# Shield.net
KiCad netlist of a schematic drawn in EAGLE
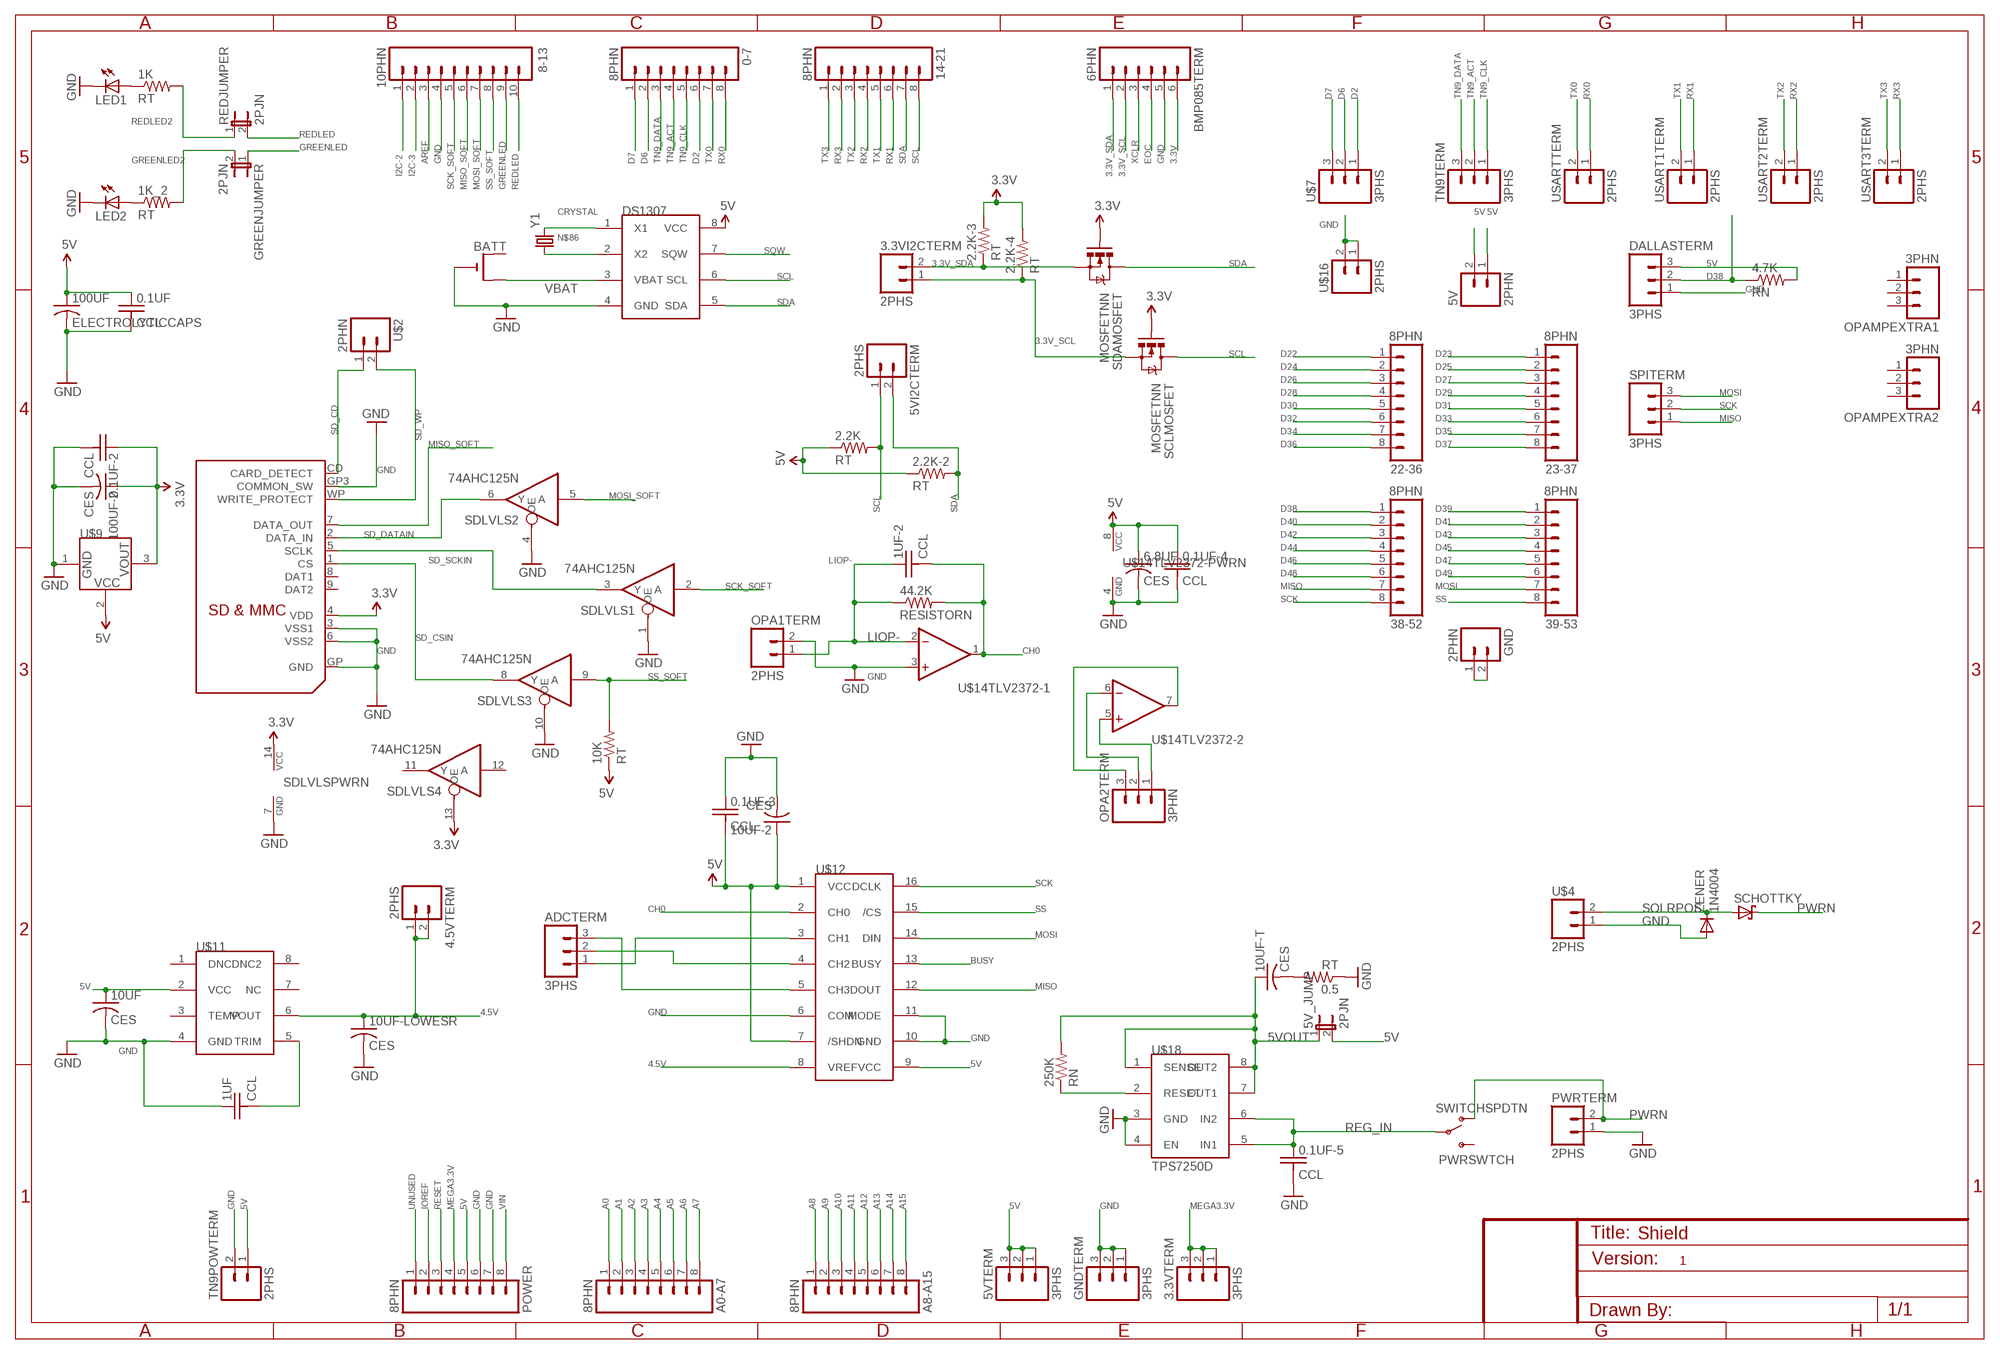
[diagram p0: schematic, sheet 1]

(export (version "E")
  (design (tool "Eeschema 10.0.6"))
  (components
    (comp (ref "0-7")
      (value "8PHN")
      (footprint "eagle-import:8PH")
      (libsource (lib "eagle-import") (part "8PHN"))
    )
    (comp (ref "0.1UF")
      (value "CCL")
      (footprint "eagle-import:C025-025X050")
      (libsource (lib "eagle-import") (part "CCL"))
    )
    (comp (ref "0.1UF-2")
      (value "CCL")
      (footprint "eagle-import:C025-025X050")
      (libsource (lib "eagle-import") (part "CCL"))
    )
    (comp (ref "0.1UF-3")
      (value "CCL")
      (footprint "eagle-import:C025-025X050")
      (libsource (lib "eagle-import") (part "CCL"))
    )
    (comp (ref "0.1UF-4")
      (value "CCL")
      (footprint "eagle-import:C025-025X050")
      (libsource (lib "eagle-import") (part "CCL"))
    )
    (comp (ref "0.1UF-5")
      (value "CCL")
      (footprint "eagle-import:C025-025X050")
      (libsource (lib "eagle-import") (part "CCL"))
    )
    (comp (ref "0.5")
      (value "RT")
      (footprint "eagle-import:0207_7")
      (libsource (lib "eagle-import") (part "RT"))
    )
    (comp (ref "1K")
      (value "RT")
      (footprint "eagle-import:0207_7")
      (libsource (lib "eagle-import") (part "RT"))
    )
    (comp (ref "1K_2")
      (value "RT")
      (footprint "eagle-import:0207_7")
      (libsource (lib "eagle-import") (part "RT"))
    )
    (comp (ref "1UF")
      (value "CCL")
      (footprint "eagle-import:C025-025X050")
      (libsource (lib "eagle-import") (part "CCL"))
    )
    (comp (ref "1UF-2")
      (value "CCL")
      (footprint "eagle-import:C025-025X050")
      (libsource (lib "eagle-import") (part "CCL"))
    )
    (comp (ref "2.2K")
      (value "RT")
      (footprint "eagle-import:0207_7")
      (libsource (lib "eagle-import") (part "RT"))
    )
    (comp (ref "2.2K-2")
      (value "RT")
      (footprint "eagle-import:0207_7")
      (libsource (lib "eagle-import") (part "RT"))
    )
    (comp (ref "2.2K-3")
      (value "RT")
      (footprint "eagle-import:0207_7")
      (libsource (lib "eagle-import") (part "RT"))
    )
    (comp (ref "2.2K-4")
      (value "RT")
      (footprint "eagle-import:0207_7")
      (libsource (lib "eagle-import") (part "RT"))
    )
    (comp (ref "3.3VI2CTERM")
      (value "2PHS")
      (footprint "eagle-import:SCREWTERMINAL-3.5MM-2_LOCK")
      (libsource (lib "eagle-import") (part "2PHS"))
    )
    (comp (ref "3.3VTERM")
      (value "3PHS")
      (footprint "eagle-import:SCREWTERMINAL-3.5MM-3_LOCK.007S")
      (libsource (lib "eagle-import") (part "3PHS"))
    )
    (comp (ref "4.5VTERM")
      (value "2PHS")
      (footprint "eagle-import:SCREWTERMINAL-3.5MM-2_LOCK")
      (libsource (lib "eagle-import") (part "2PHS"))
    )
    (comp (ref "4.7K")
      (value "RN")
      (footprint "eagle-import:0207_10")
      (libsource (lib "eagle-import") (part "RN"))
    )
    (comp (ref "5V")
      (value "2PHN")
      (footprint "eagle-import:2PH")
      (libsource (lib "eagle-import") (part "2PHN"))
    )
    (comp (ref "5VI2CTERM")
      (value "2PHS")
      (footprint "eagle-import:SCREWTERMINAL-3.5MM-2_LOCK")
      (libsource (lib "eagle-import") (part "2PHS"))
    )
    (comp (ref "5VTERM")
      (value "3PHS")
      (footprint "eagle-import:SCREWTERMINAL-3.5MM-3_LOCK.007S")
      (libsource (lib "eagle-import") (part "3PHS"))
    )
    (comp (ref "5V_JUMP")
      (value "2PJN")
      (footprint "eagle-import:2PH")
      (libsource (lib "eagle-import") (part "2PJN"))
    )
    (comp (ref "6.8UF")
      (value "CES")
      (footprint "eagle-import:E2,5-5")
      (libsource (lib "eagle-import") (part "CES"))
    )
    (comp (ref "8-13")
      (value "10PHN")
      (footprint "eagle-import:10PH")
      (libsource (lib "eagle-import") (part "10PHN"))
    )
    (comp (ref "10K")
      (value "RT")
      (footprint "eagle-import:0207_7")
      (libsource (lib "eagle-import") (part "RT"))
    )
    (comp (ref "10UF")
      (value "CES")
      (footprint "eagle-import:E2,5-5")
      (libsource (lib "eagle-import") (part "CES"))
    )
    (comp (ref "10UF-2")
      (value "CES")
      (footprint "eagle-import:E2,5-5")
      (libsource (lib "eagle-import") (part "CES"))
    )
    (comp (ref "10UF-LOWESR")
      (value "CES")
      (footprint "eagle-import:E2,5-5")
      (libsource (lib "eagle-import") (part "CES"))
    )
    (comp (ref "10UF-T")
      (value "CES")
      (footprint "eagle-import:E2,5-5")
      (libsource (lib "eagle-import") (part "CES"))
    )
    (comp (ref "14-21")
      (value "8PHN")
      (footprint "eagle-import:8PH")
      (libsource (lib "eagle-import") (part "8PHN"))
    )
    (comp (ref "22-36")
      (value "8PHN")
      (footprint "eagle-import:8PH")
      (libsource (lib "eagle-import") (part "8PHN"))
    )
    (comp (ref "23-37")
      (value "8PHN")
      (footprint "eagle-import:8PH")
      (libsource (lib "eagle-import") (part "8PHN"))
    )
    (comp (ref "38-52")
      (value "8PHN")
      (footprint "eagle-import:8PH")
      (libsource (lib "eagle-import") (part "8PHN"))
    )
    (comp (ref "39-53")
      (value "8PHN")
      (footprint "eagle-import:8PH")
      (libsource (lib "eagle-import") (part "8PHN"))
    )
    (comp (ref "44.2K")
      (value "RESISTORN")
      (footprint "eagle-import:0207_10")
      (libsource (lib "eagle-import") (part "RESISTORN"))
    )
    (comp (ref "100UF")
      (value "ELECTROLYTICCAPS")
      (footprint "eagle-import:E2,5-5")
      (libsource (lib "eagle-import") (part "ELECTROLYTICCAPS"))
    )
    (comp (ref "100UF-2")
      (value "CES")
      (footprint "eagle-import:E2,5-5")
      (libsource (lib "eagle-import") (part "CES"))
    )
    (comp (ref "250K")
      (value "RN")
      (footprint "eagle-import:0207_10")
      (libsource (lib "eagle-import") (part "RN"))
    )
    (comp (ref "A0-A7")
      (value "8PHN")
      (footprint "eagle-import:8PH")
      (libsource (lib "eagle-import") (part "8PHN"))
    )
    (comp (ref "A8-A15")
      (value "8PHN")
      (footprint "eagle-import:8PH")
      (libsource (lib "eagle-import") (part "8PHN"))
    )
    (comp (ref "ADCTERM")
      (value "3PHS")
      (footprint "eagle-import:SCREWTERMINAL-3.5MM-3_LOCK.007S")
      (libsource (lib "eagle-import") (part "3PHS"))
    )
    (comp (ref "BATT")
      (value "CR1220THM")
      (footprint "eagle-import:CR1220-THM")
      (libsource (lib "eagle-import") (part "CR1220THM"))
    )
    (comp (ref "BMP085TERM")
      (value "6PHN")
      (footprint "eagle-import:6PH")
      (libsource (lib "eagle-import") (part "6PHN"))
    )
    (comp (ref "DALLASTERM")
      (value "3PHS")
      (footprint "eagle-import:SCREWTERMINAL-3.5MM-3_LOCK.007S")
      (libsource (lib "eagle-import") (part "3PHS"))
    )
    (comp (ref "DS1307")
      (value "DS1307P")
      (footprint "eagle-import:DIL8")
      (libsource (lib "eagle-import") (part "DS1307P"))
    )
    (comp (ref "GND")
      (value "2PHN")
      (footprint "eagle-import:2PH")
      (libsource (lib "eagle-import") (part "2PHN"))
    )
    (comp (ref "GNDTERM")
      (value "3PHS")
      (footprint "eagle-import:SCREWTERMINAL-3.5MM-3_LOCK.007S")
      (libsource (lib "eagle-import") (part "3PHS"))
    )
    (comp (ref "GREENJUMPER")
      (value "2PJN")
      (footprint "eagle-import:2PH")
      (libsource (lib "eagle-import") (part "2PJN"))
    )
    (comp (ref "LED1")
      (value "LED3MM")
      (footprint "eagle-import:LED3MM")
      (libsource (lib "eagle-import") (part "LED3MM"))
    )
    (comp (ref "LED2")
      (value "LED3MM")
      (footprint "eagle-import:LED3MM")
      (libsource (lib "eagle-import") (part "LED3MM"))
    )
    (comp (ref "OPA1TERM")
      (value "2PHS")
      (footprint "eagle-import:SCREWTERMINAL-3.5MM-2_LOCK")
      (libsource (lib "eagle-import") (part "2PHS"))
    )
    (comp (ref "OPA2TERM")
      (value "3PHN")
      (footprint "eagle-import:3PH")
      (libsource (lib "eagle-import") (part "3PHN"))
    )
    (comp (ref "OPAMPEXTRA1")
      (value "3PHN")
      (footprint "eagle-import:3PH")
      (libsource (lib "eagle-import") (part "3PHN"))
    )
    (comp (ref "OPAMPEXTRA2")
      (value "3PHN")
      (footprint "eagle-import:3PH")
      (libsource (lib "eagle-import") (part "3PHN"))
    )
    (comp (ref "POWER")
      (value "8PHN")
      (footprint "eagle-import:8PH")
      (libsource (lib "eagle-import") (part "8PHN"))
    )
    (comp (ref "PWRSWTCH")
      (value "SWITCHSPDTN")
      (footprint "eagle-import:SWITCH-SPDT")
      (libsource (lib "eagle-import") (part "SWITCHSPDTN"))
    )
    (comp (ref "PWRTERM")
      (value "2PHS")
      (footprint "eagle-import:SCREWTERMINAL-3.5MM-2_LOCK")
      (libsource (lib "eagle-import") (part "2PHS"))
    )
    (comp (ref "REDJUMPER")
      (value "2PJN")
      (footprint "eagle-import:2PH")
      (libsource (lib "eagle-import") (part "2PJN"))
    )
    (comp (ref "SCHOTTKY")
      (value "SCHOTTKY-DIODEDO41")
      (footprint "eagle-import:DO41-10")
      (libsource (lib "eagle-import") (part "SCHOTTKY-DIODEDO41"))
    )
    (comp (ref "SCLMOSFET")
      (value "MOSFETNN")
      (footprint "eagle-import:TO-92INLINE")
      (libsource (lib "eagle-import") (part "MOSFETNN"))
    )
    (comp (ref "SDAMOSFET")
      (value "MOSFETNN")
      (footprint "eagle-import:TO-92INLINE")
      (libsource (lib "eagle-import") (part "MOSFETNN"))
    )
    (comp (ref "SDLVLS")
      (value "74AHC125N")
      (footprint "eagle-import:DIL14")
      (libsource (lib "eagle-import") (part "74AHC125N"))
    )
    (comp (ref "SPITERM")
      (value "3PHS")
      (footprint "eagle-import:SCREWTERMINAL-3.5MM-3_LOCK.007S")
      (libsource (lib "eagle-import") (part "3PHS"))
    )
    (comp (ref "TN9POWTERM")
      (value "2PHS")
      (footprint "eagle-import:SCREWTERMINAL-3.5MM-2_LOCK")
      (libsource (lib "eagle-import") (part "2PHS"))
    )
    (comp (ref "TN9TERM")
      (value "3PHS")
      (footprint "eagle-import:SCREWTERMINAL-3.5MM-3_LOCK.007S")
      (libsource (lib "eagle-import") (part "3PHS"))
    )
    (comp (ref "U$1")
      (value "SDMMC06132")
      (footprint "eagle-import:06132")
      (libsource (lib "eagle-import") (part "SDMMC06132"))
    )
    (comp (ref "U$2")
      (value "2PHN")
      (footprint "eagle-import:2PH")
      (libsource (lib "eagle-import") (part "2PHN"))
    )
    (comp (ref "U$4")
      (value "2PHS")
      (footprint "eagle-import:SCREWTERMINAL-3.5MM-2_LOCK")
      (libsource (lib "eagle-import") (part "2PHS"))
    )
    (comp (ref "U$7")
      (value "3PHS")
      (footprint "eagle-import:SCREWTERMINAL-3.5MM-3_LOCK.007S")
      (libsource (lib "eagle-import") (part "3PHS"))
    )
    (comp (ref "U$9")
      (value "MCP1700-330T")
      (footprint "eagle-import:TO-92INLINE")
      (libsource (lib "eagle-import") (part "MCP1700-330T"))
    )
    (comp (ref "U$11")
      (value "REF5045S")
      (footprint "eagle-import:SOIC8")
      (libsource (lib "eagle-import") (part "REF5045S"))
    )
    (comp (ref "U$12")
      (value "ADS7841P")
      (footprint "eagle-import:DIL16")
      (libsource (lib "eagle-import") (part "ADS7841P"))
    )
    (comp (ref "U$14")
      (value "TLV2372P")
      (footprint "eagle-import:DIL8")
      (libsource (lib "eagle-import") (part "TLV2372P"))
    )
    (comp (ref "U$16")
      (value "2PHS")
      (footprint "eagle-import:SCREWTERMINAL-3.5MM-2_LOCK")
      (libsource (lib "eagle-import") (part "2PHS"))
    )
    (comp (ref "U$18")
      (value "TPS7250D")
      (footprint "eagle-import:DIL8")
      (libsource (lib "eagle-import") (part "TPS7250D"))
    )
    (comp (ref "USART1TERM")
      (value "2PHS")
      (footprint "eagle-import:SCREWTERMINAL-3.5MM-2_LOCK")
      (libsource (lib "eagle-import") (part "2PHS"))
    )
    (comp (ref "USART2TERM")
      (value "2PHS")
      (footprint "eagle-import:SCREWTERMINAL-3.5MM-2_LOCK")
      (libsource (lib "eagle-import") (part "2PHS"))
    )
    (comp (ref "USART3TERM")
      (value "2PHS")
      (footprint "eagle-import:SCREWTERMINAL-3.5MM-2_LOCK")
      (libsource (lib "eagle-import") (part "2PHS"))
    )
    (comp (ref "USARTTERM")
      (value "2PHS")
      (footprint "eagle-import:SCREWTERMINAL-3.5MM-2_LOCK")
      (libsource (lib "eagle-import") (part "2PHS"))
    )
    (comp (ref "Y1")
      (value "CRYSTALTC38H")
      (footprint "eagle-import:TC38H")
      (libsource (lib "eagle-import") (part "CRYSTALTC38H"))
    )
    (comp (ref "ZENER")
      (value "1N4004")
      (footprint "eagle-import:DO41-10")
      (libsource (lib "eagle-import") (part "1N4004"))
    )
  )
  (nets
    (net (code "1") (name "/3.3V_SCL") (class "Default")
      (node (ref "2.2K-4") (pin "1") (pinfunction "1_1") (pintype "passive"))
      (node (ref "3.3VI2CTERM") (pin "1") (pinfunction "1_1") (pintype "passive"))
      (node (ref "BMP085TERM") (pin "2") (pinfunction "2_2") (pintype "passive"))
      (node (ref "SCLMOSFET") (pin "1") (pinfunction "S_1") (pintype "passive"))
    )
    (net (code "2") (name "/3.3V_SDA") (class "Default")
      (node (ref "2.2K-3") (pin "1") (pinfunction "1_1") (pintype "passive"))
      (node (ref "3.3VI2CTERM") (pin "2") (pinfunction "2_2") (pintype "passive"))
      (node (ref "BMP085TERM") (pin "1") (pinfunction "1_1") (pintype "passive"))
      (node (ref "SDAMOSFET") (pin "1") (pinfunction "S_1") (pintype "passive"))
    )
    (net (code "3") (name "/4.5V") (class "Default")
      (node (ref "10UF-LOWESR") (pin "+") (pinfunction "1_+") (pintype "passive"))
      (node (ref "4.5VTERM") (pin "1") (pinfunction "1_1") (pintype "passive"))
      (node (ref "4.5VTERM") (pin "2") (pinfunction "2_2") (pintype "passive"))
      (node (ref "U$11") (pin "6") (pinfunction "VOUT_6") (pintype "output"))
      (node (ref "U$12") (pin "8") (pinfunction "VREF_8") (pintype "input"))
    )
    (net (code "4") (name "/5VOUT") (class "Default")
      (node (ref "10UF-T") (pin "+") (pinfunction "1_+") (pintype "passive"))
      (node (ref "250K") (pin "2") (pinfunction "2_2") (pintype "passive"))
      (node (ref "5V_JUMP") (pin "1") (pinfunction "1_1") (pintype "passive"))
      (node (ref "U$18") (pin "1") (pinfunction "SENSE_1") (pintype "bidirectional"))
      (node (ref "U$18") (pin "7") (pinfunction "OUT1_7") (pintype "output"))
      (node (ref "U$18") (pin "8") (pinfunction "OUT2_8") (pintype "output"))
    )
    (net (code "5") (name "/A0") (class "Default")
      (node (ref "A0-A7") (pin "1") (pinfunction "1_1") (pintype "passive"))
    )
    (net (code "6") (name "/A1") (class "Default")
      (node (ref "A0-A7") (pin "2") (pinfunction "2_2") (pintype "passive"))
    )
    (net (code "7") (name "/A2") (class "Default")
      (node (ref "A0-A7") (pin "3") (pinfunction "3_3") (pintype "passive"))
    )
    (net (code "8") (name "/A3") (class "Default")
      (node (ref "A0-A7") (pin "4") (pinfunction "4_4") (pintype "passive"))
    )
    (net (code "9") (name "/A4") (class "Default")
      (node (ref "A0-A7") (pin "5") (pinfunction "5_5") (pintype "passive"))
    )
    (net (code "10") (name "/A5") (class "Default")
      (node (ref "A0-A7") (pin "6") (pinfunction "6_6") (pintype "passive"))
    )
    (net (code "11") (name "/A6") (class "Default")
      (node (ref "A0-A7") (pin "7") (pinfunction "7_7") (pintype "passive"))
    )
    (net (code "12") (name "/A7") (class "Default")
      (node (ref "A0-A7") (pin "8") (pinfunction "8_8") (pintype "passive"))
    )
    (net (code "13") (name "/A8") (class "Default")
      (node (ref "A8-A15") (pin "1") (pinfunction "1_1") (pintype "passive"))
    )
    (net (code "14") (name "/A9") (class "Default")
      (node (ref "A8-A15") (pin "2") (pinfunction "2_2") (pintype "passive"))
    )
    (net (code "15") (name "/A10") (class "Default")
      (node (ref "A8-A15") (pin "3") (pinfunction "3_3") (pintype "passive"))
    )
    (net (code "16") (name "/A11") (class "Default")
      (node (ref "A8-A15") (pin "4") (pinfunction "4_4") (pintype "passive"))
    )
    (net (code "17") (name "/A12") (class "Default")
      (node (ref "A8-A15") (pin "5") (pinfunction "5_5") (pintype "passive"))
    )
    (net (code "18") (name "/A13") (class "Default")
      (node (ref "A8-A15") (pin "6") (pinfunction "6_6") (pintype "passive"))
    )
    (net (code "19") (name "/A14") (class "Default")
      (node (ref "A8-A15") (pin "7") (pinfunction "7_7") (pintype "passive"))
    )
    (net (code "20") (name "/A15") (class "Default")
      (node (ref "A8-A15") (pin "8") (pinfunction "8_8") (pintype "passive"))
    )
    (net (code "21") (name "/AREF") (class "Default")
      (node (ref "8-13") (pin "3") (pinfunction "3_3") (pintype "passive"))
    )
    (net (code "22") (name "/BUSY") (class "Default")
      (node (ref "U$12") (pin "13") (pinfunction "BUSY_13") (pintype "output"))
    )
    (net (code "23") (name "/CH0") (class "Default")
      (node (ref "1UF-2") (pin "2") (pinfunction "2_2") (pintype "passive"))
      (node (ref "44.2K") (pin "2") (pinfunction "2_2") (pintype "passive"))
      (node (ref "U$12") (pin "2") (pinfunction "CH0_2") (pintype "input"))
      (node (ref "U$14") (pin "1") (pinfunction "OUT_1") (pintype "output"))
    )
    (net (code "24") (name "/CRYSTAL") (class "Default")
      (node (ref "DS1307") (pin "1") (pinfunction "X1_1") (pintype "input"))
      (node (ref "Y1") (pin "2") (pinfunction "2_2") (pintype "passive"))
    )
    (net (code "25") (name "/D2") (class "Default")
      (node (ref "0-7") (pin "6") (pinfunction "6_6") (pintype "passive"))
      (node (ref "U$7") (pin "1") (pinfunction "1_1") (pintype "passive"))
    )
    (net (code "26") (name "/D6") (class "Default")
      (node (ref "0-7") (pin "2") (pinfunction "2_2") (pintype "passive"))
      (node (ref "U$7") (pin "2") (pinfunction "2_2") (pintype "passive"))
    )
    (net (code "27") (name "/D7") (class "Default")
      (node (ref "0-7") (pin "1") (pinfunction "1_1") (pintype "passive"))
      (node (ref "U$7") (pin "3") (pinfunction "3_3") (pintype "passive"))
    )
    (net (code "28") (name "/D22") (class "Default")
      (node (ref "22-36") (pin "1") (pinfunction "1_1") (pintype "passive"))
    )
    (net (code "29") (name "/D23") (class "Default")
      (node (ref "23-37") (pin "1") (pinfunction "1_1") (pintype "passive"))
    )
    (net (code "30") (name "/D24") (class "Default")
      (node (ref "22-36") (pin "2") (pinfunction "2_2") (pintype "passive"))
    )
    (net (code "31") (name "/D25") (class "Default")
      (node (ref "23-37") (pin "2") (pinfunction "2_2") (pintype "passive"))
    )
    (net (code "32") (name "/D26") (class "Default")
      (node (ref "22-36") (pin "3") (pinfunction "3_3") (pintype "passive"))
    )
    (net (code "33") (name "/D27") (class "Default")
      (node (ref "23-37") (pin "3") (pinfunction "3_3") (pintype "passive"))
    )
    (net (code "34") (name "/D28") (class "Default")
      (node (ref "22-36") (pin "4") (pinfunction "4_4") (pintype "passive"))
    )
    (net (code "35") (name "/D29") (class "Default")
      (node (ref "23-37") (pin "4") (pinfunction "4_4") (pintype "passive"))
    )
    (net (code "36") (name "/D30") (class "Default")
      (node (ref "22-36") (pin "5") (pinfunction "5_5") (pintype "passive"))
    )
    (net (code "37") (name "/D31") (class "Default")
      (node (ref "23-37") (pin "5") (pinfunction "5_5") (pintype "passive"))
    )
    (net (code "38") (name "/D32") (class "Default")
      (node (ref "22-36") (pin "6") (pinfunction "6_6") (pintype "passive"))
    )
    (net (code "39") (name "/D33") (class "Default")
      (node (ref "23-37") (pin "6") (pinfunction "6_6") (pintype "passive"))
    )
    (net (code "40") (name "/D34") (class "Default")
      (node (ref "22-36") (pin "7") (pinfunction "7_7") (pintype "passive"))
    )
    (net (code "41") (name "/D35") (class "Default")
      (node (ref "23-37") (pin "7") (pinfunction "7_7") (pintype "passive"))
    )
    (net (code "42") (name "/D36") (class "Default")
      (node (ref "22-36") (pin "8") (pinfunction "8_8") (pintype "passive"))
    )
    (net (code "43") (name "/D37") (class "Default")
      (node (ref "23-37") (pin "8") (pinfunction "8_8") (pintype "passive"))
    )
    (net (code "44") (name "/D38") (class "Default")
      (node (ref "38-52") (pin "1") (pinfunction "1_1") (pintype "passive"))
      (node (ref "4.7K") (pin "1") (pinfunction "1_1") (pintype "passive"))
      (node (ref "DALLASTERM") (pin "2") (pinfunction "2_2") (pintype "passive"))
    )
    (net (code "45") (name "/D39") (class "Default")
      (node (ref "39-53") (pin "1") (pinfunction "1_1") (pintype "passive"))
    )
    (net (code "46") (name "/D40") (class "Default")
      (node (ref "38-52") (pin "2") (pinfunction "2_2") (pintype "passive"))
    )
    (net (code "47") (name "/D41") (class "Default")
      (node (ref "39-53") (pin "2") (pinfunction "2_2") (pintype "passive"))
    )
    (net (code "48") (name "/D42") (class "Default")
      (node (ref "38-52") (pin "3") (pinfunction "3_3") (pintype "passive"))
    )
    (net (code "49") (name "/D43") (class "Default")
      (node (ref "39-53") (pin "3") (pinfunction "3_3") (pintype "passive"))
    )
    (net (code "50") (name "/D44") (class "Default")
      (node (ref "38-52") (pin "4") (pinfunction "4_4") (pintype "passive"))
    )
    (net (code "51") (name "/D45") (class "Default")
      (node (ref "39-53") (pin "4") (pinfunction "4_4") (pintype "passive"))
    )
    (net (code "52") (name "/D46") (class "Default")
      (node (ref "38-52") (pin "5") (pinfunction "5_5") (pintype "passive"))
    )
    (net (code "53") (name "/D47") (class "Default")
      (node (ref "39-53") (pin "5") (pinfunction "5_5") (pintype "passive"))
    )
    (net (code "54") (name "/D48") (class "Default")
      (node (ref "38-52") (pin "6") (pinfunction "6_6") (pintype "passive"))
    )
    (net (code "55") (name "/D49") (class "Default")
      (node (ref "39-53") (pin "6") (pinfunction "6_6") (pintype "passive"))
    )
    (net (code "56") (name "/EOC") (class "Default")
      (node (ref "BMP085TERM") (pin "4") (pinfunction "4_4") (pintype "passive"))
    )
    (net (code "57") (name "/GREENLED") (class "Default")
      (node (ref "8-13") (pin "9") (pinfunction "9_9") (pintype "passive"))
      (node (ref "GREENJUMPER") (pin "1") (pinfunction "1_1") (pintype "passive"))
    )
    (net (code "58") (name "/GREENLED2") (class "Default")
      (node (ref "1K_2") (pin "2") (pinfunction "2_2") (pintype "passive"))
      (node (ref "GREENJUMPER") (pin "2") (pinfunction "2_2") (pintype "passive"))
    )
    (net (code "59") (name "/I2C-2") (class "Default")
      (node (ref "8-13") (pin "1") (pinfunction "1_1") (pintype "passive"))
    )
    (net (code "60") (name "/I2C-3") (class "Default")
      (node (ref "8-13") (pin "2") (pinfunction "2_2") (pintype "passive"))
    )
    (net (code "61") (name "/IOREF") (class "Default")
      (node (ref "POWER") (pin "2") (pinfunction "2_2") (pintype "passive"))
    )
    (net (code "62") (name "/LIOP-") (class "Default")
      (node (ref "1UF-2") (pin "1") (pinfunction "1_1") (pintype "passive"))
      (node (ref "44.2K") (pin "1") (pinfunction "1_1") (pintype "passive"))
      (node (ref "OPA1TERM") (pin "1") (pinfunction "1_1") (pintype "passive"))
      (node (ref "U$14") (pin "2") (pinfunction "-IN_2") (pintype "input"))
    )
    (net (code "63") (name "/MEGA3.3V") (class "Default")
      (node (ref "3.3VTERM") (pin "1") (pinfunction "1_1") (pintype "passive"))
      (node (ref "3.3VTERM") (pin "2") (pinfunction "2_2") (pintype "passive"))
      (node (ref "3.3VTERM") (pin "3") (pinfunction "3_3") (pintype "passive"))
      (node (ref "POWER") (pin "4") (pinfunction "4_4") (pintype "passive"))
    )
    (net (code "64") (name "/MISO") (class "Default")
      (node (ref "38-52") (pin "7") (pinfunction "7_7") (pintype "passive"))
      (node (ref "SPITERM") (pin "1") (pinfunction "1_1") (pintype "passive"))
      (node (ref "U$12") (pin "12") (pinfunction "DOUT_12") (pintype "output"))
    )
    (net (code "65") (name "/MISO_SOFT") (class "Default")
      (node (ref "8-13") (pin "6") (pinfunction "6_6") (pintype "passive"))
      (node (ref "U$1") (pin "7") (pinfunction "DATA_OUT_7") (pintype "output"))
    )
    (net (code "66") (name "/MOSI") (class "Default")
      (node (ref "39-53") (pin "7") (pinfunction "7_7") (pintype "passive"))
      (node (ref "SPITERM") (pin "3") (pinfunction "3_3") (pintype "passive"))
      (node (ref "U$12") (pin "14") (pinfunction "DIN_14") (pintype "input"))
    )
    (net (code "67") (name "/MOSI_SOFT") (class "Default")
      (node (ref "8-13") (pin "7") (pinfunction "7_7") (pintype "passive"))
      (node (ref "SDLVLS") (pin "5") (pinfunction "A_5") (pintype "input"))
    )
    (net (code "68") (name "/N$86") (class "Default")
      (node (ref "DS1307") (pin "2") (pinfunction "X2_2") (pintype "input"))
      (node (ref "Y1") (pin "1") (pinfunction "1_1") (pintype "passive"))
    )
    (net (code "69") (name "/PWRN") (class "Default")
      (node (ref "PWRSWTCH") (pin "1") (pinfunction "O_1") (pintype "passive"))
      (node (ref "PWRTERM") (pin "2") (pinfunction "2_2") (pintype "passive"))
      (node (ref "SCHOTTKY") (pin "C") (pinfunction "C_C") (pintype "passive"))
    )
    (net (code "70") (name "/REDLED") (class "Default")
      (node (ref "8-13") (pin "10") (pinfunction "10_10") (pintype "passive"))
      (node (ref "REDJUMPER") (pin "2") (pinfunction "2_2") (pintype "passive"))
    )
    (net (code "71") (name "/REDLED2") (class "Default")
      (node (ref "1K") (pin "2") (pinfunction "2_2") (pintype "passive"))
      (node (ref "REDJUMPER") (pin "1") (pinfunction "1_1") (pintype "passive"))
    )
    (net (code "72") (name "/REG_IN") (class "Default")
      (node (ref "0.1UF-5") (pin "1") (pinfunction "1_1") (pintype "passive"))
      (node (ref "PWRSWTCH") (pin "2") (pinfunction "P_2") (pintype "passive"))
      (node (ref "U$18") (pin "5") (pinfunction "IN1_5") (pintype "power_in"))
      (node (ref "U$18") (pin "6") (pinfunction "IN2_6") (pintype "power_in"))
    )
    (net (code "73") (name "/RESET") (class "Default")
      (node (ref "POWER") (pin "3") (pinfunction "3_3") (pintype "passive"))
    )
    (net (code "74") (name "/RX0") (class "Default")
      (node (ref "0-7") (pin "8") (pinfunction "8_8") (pintype "passive"))
      (node (ref "USARTTERM") (pin "1") (pinfunction "1_1") (pintype "passive"))
    )
    (net (code "75") (name "/RX1") (class "Default")
      (node (ref "14-21") (pin "6") (pinfunction "6_6") (pintype "passive"))
      (node (ref "USART1TERM") (pin "1") (pinfunction "1_1") (pintype "passive"))
    )
    (net (code "76") (name "/RX2") (class "Default")
      (node (ref "14-21") (pin "4") (pinfunction "4_4") (pintype "passive"))
      (node (ref "USART2TERM") (pin "1") (pinfunction "1_1") (pintype "passive"))
    )
    (net (code "77") (name "/RX3") (class "Default")
      (node (ref "14-21") (pin "2") (pinfunction "2_2") (pintype "passive"))
      (node (ref "USART3TERM") (pin "1") (pinfunction "1_1") (pintype "passive"))
    )
    (net (code "78") (name "/SCK") (class "Default")
      (node (ref "38-52") (pin "8") (pinfunction "8_8") (pintype "passive"))
      (node (ref "SPITERM") (pin "2") (pinfunction "2_2") (pintype "passive"))
      (node (ref "U$12") (pin "16") (pinfunction "DCLK_16") (pintype "input"))
    )
    (net (code "79") (name "/SCK_SOFT") (class "Default")
      (node (ref "8-13") (pin "5") (pinfunction "5_5") (pintype "passive"))
      (node (ref "SDLVLS") (pin "2") (pinfunction "A_2") (pintype "input"))
    )
    (net (code "80") (name "/SCL") (class "Default")
      (node (ref "14-21") (pin "8") (pinfunction "8_8") (pintype "passive"))
      (node (ref "2.2K") (pin "2") (pinfunction "2_2") (pintype "passive"))
      (node (ref "5VI2CTERM") (pin "1") (pinfunction "1_1") (pintype "passive"))
      (node (ref "DS1307") (pin "6") (pinfunction "SCL_6") (pintype "input"))
      (node (ref "SCLMOSFET") (pin "3") (pinfunction "D_3") (pintype "passive"))
    )
    (net (code "81") (name "/SDA") (class "Default")
      (node (ref "14-21") (pin "7") (pinfunction "7_7") (pintype "passive"))
      (node (ref "2.2K-2") (pin "2") (pinfunction "2_2") (pintype "passive"))
      (node (ref "5VI2CTERM") (pin "2") (pinfunction "2_2") (pintype "passive"))
      (node (ref "DS1307") (pin "5") (pinfunction "SDA_5") (pintype "bidirectional"))
      (node (ref "SDAMOSFET") (pin "3") (pinfunction "D_3") (pintype "passive"))
    )
    (net (code "82") (name "/SD_CD") (class "Default")
      (node (ref "U$1") (pin "CD") (pinfunction "CARD_DETECT_CD") (pintype "passive"))
      (node (ref "U$2") (pin "1") (pinfunction "1_1") (pintype "passive"))
    )
    (net (code "83") (name "/SD_CSIN") (class "Default")
      (node (ref "SDLVLS") (pin "8") (pinfunction "Y_8") (pintype "tri_state"))
      (node (ref "U$1") (pin "1") (pinfunction "CS_1") (pintype "input"))
    )
    (net (code "84") (name "/SD_DATAIN") (class "Default")
      (node (ref "SDLVLS") (pin "6") (pinfunction "Y_6") (pintype "tri_state"))
      (node (ref "U$1") (pin "2") (pinfunction "DATA_IN_2") (pintype "input"))
    )
    (net (code "85") (name "/SD_SCKIN") (class "Default")
      (node (ref "SDLVLS") (pin "3") (pinfunction "Y_3") (pintype "tri_state"))
      (node (ref "U$1") (pin "5") (pinfunction "SCLK_5") (pintype "input"))
    )
    (net (code "86") (name "/SD_WP") (class "Default")
      (node (ref "U$1") (pin "WP") (pinfunction "WRITE_PROTECT_WP") (pintype "passive"))
      (node (ref "U$2") (pin "2") (pinfunction "2_2") (pintype "passive"))
    )
    (net (code "87") (name "/SOLRPOS") (class "Default")
      (node (ref "SCHOTTKY") (pin "A") (pinfunction "A_A") (pintype "passive"))
      (node (ref "U$4") (pin "2") (pinfunction "2_2") (pintype "passive"))
      (node (ref "ZENER") (pin "C") (pinfunction "C_C") (pintype "passive"))
    )
    (net (code "88") (name "/SQW") (class "Default")
      (node (ref "DS1307") (pin "7") (pinfunction "SQW_7") (pintype "output"))
    )
    (net (code "89") (name "/SS") (class "Default")
      (node (ref "39-53") (pin "8") (pinfunction "8_8") (pintype "passive"))
      (node (ref "U$12") (pin "15") (pinfunction "/CS_15") (pintype "input"))
    )
    (net (code "90") (name "/SS_SOFT") (class "Default")
      (node (ref "10K") (pin "2") (pinfunction "2_2") (pintype "passive"))
      (node (ref "8-13") (pin "8") (pinfunction "8_8") (pintype "passive"))
      (node (ref "SDLVLS") (pin "9") (pinfunction "A_9") (pintype "input"))
    )
    (net (code "91") (name "/TN9_ACT") (class "Default")
      (node (ref "0-7") (pin "4") (pinfunction "4_4") (pintype "passive"))
      (node (ref "TN9TERM") (pin "2") (pinfunction "2_2") (pintype "passive"))
    )
    (net (code "92") (name "/TN9_CLK") (class "Default")
      (node (ref "0-7") (pin "5") (pinfunction "5_5") (pintype "passive"))
      (node (ref "TN9TERM") (pin "1") (pinfunction "1_1") (pintype "passive"))
    )
    (net (code "93") (name "/TN9_DATA") (class "Default")
      (node (ref "0-7") (pin "3") (pinfunction "3_3") (pintype "passive"))
      (node (ref "TN9TERM") (pin "3") (pinfunction "3_3") (pintype "passive"))
    )
    (net (code "94") (name "/TX0") (class "Default")
      (node (ref "0-7") (pin "7") (pinfunction "7_7") (pintype "passive"))
      (node (ref "USARTTERM") (pin "2") (pinfunction "2_2") (pintype "passive"))
    )
    (net (code "95") (name "/TX1") (class "Default")
      (node (ref "14-21") (pin "5") (pinfunction "5_5") (pintype "passive"))
      (node (ref "USART1TERM") (pin "2") (pinfunction "2_2") (pintype "passive"))
    )
    (net (code "96") (name "/TX2") (class "Default")
      (node (ref "14-21") (pin "3") (pinfunction "3_3") (pintype "passive"))
      (node (ref "USART2TERM") (pin "2") (pinfunction "2_2") (pintype "passive"))
    )
    (net (code "97") (name "/TX3") (class "Default")
      (node (ref "14-21") (pin "1") (pinfunction "1_1") (pintype "passive"))
      (node (ref "USART3TERM") (pin "2") (pinfunction "2_2") (pintype "passive"))
    )
    (net (code "98") (name "/UNUSED") (class "Default")
      (node (ref "POWER") (pin "1") (pinfunction "1_1") (pintype "passive"))
    )
    (net (code "99") (name "/VBAT") (class "Default")
      (node (ref "BATT") (pin "+2") (pinfunction "+1_+2") (pintype "passive"))
      (node (ref "DS1307") (pin "3") (pinfunction "VBAT_3") (pintype "power_in"))
    )
    (net (code "100") (name "/VIN") (class "Default")
      (node (ref "POWER") (pin "8") (pinfunction "8_8") (pintype "passive"))
    )
    (net (code "101") (name "/XCLR") (class "Default")
      (node (ref "BMP085TERM") (pin "3") (pinfunction "3_3") (pintype "passive"))
    )
    (net (code "102") (name "3.3V") (class "Default")
      (node (ref "0.1UF-2") (pin "1") (pinfunction "1_1") (pintype "passive"))
      (node (ref "100UF-2") (pin "+") (pinfunction "1_+") (pintype "passive"))
      (node (ref "2.2K-3") (pin "2") (pinfunction "2_2") (pintype "passive"))
      (node (ref "2.2K-4") (pin "2") (pinfunction "2_2") (pintype "passive"))
      (node (ref "BMP085TERM") (pin "6") (pinfunction "6_6") (pintype "passive"))
      (node (ref "SCLMOSFET") (pin "2") (pinfunction "G_2") (pintype "passive"))
      (node (ref "SDAMOSFET") (pin "2") (pinfunction "G_2") (pintype "passive"))
      (node (ref "SDLVLS") (pin "13") (pinfunction "OE_13") (pintype "input"))
      (node (ref "SDLVLS") (pin "14") (pinfunction "VCC_14") (pintype "power_in"))
      (node (ref "U$1") (pin "4") (pinfunction "VDD_4") (pintype "power_in"))
      (node (ref "U$9") (pin "3") (pinfunction "VOUT_3") (pintype "power_in"))
    )
    (net (code "103") (name "5V") (class "Default")
      (node (ref "0.1UF") (pin "1") (pinfunction "1_1") (pintype "passive"))
      (node (ref "0.1UF-3") (pin "2") (pinfunction "2_2") (pintype "passive"))
      (node (ref "0.1UF-4") (pin "1") (pinfunction "1_1") (pintype "passive"))
      (node (ref "100UF") (pin "+") (pinfunction "1_+") (pintype "passive"))
      (node (ref "10K") (pin "1") (pinfunction "1_1") (pintype "passive"))
      (node (ref "10UF") (pin "+") (pinfunction "1_+") (pintype "passive"))
      (node (ref "10UF-2") (pin "+") (pinfunction "1_+") (pintype "passive"))
      (node (ref "2.2K") (pin "1") (pinfunction "1_1") (pintype "passive"))
      (node (ref "2.2K-2") (pin "1") (pinfunction "1_1") (pintype "passive"))
      (node (ref "4.7K") (pin "2") (pinfunction "2_2") (pintype "passive"))
      (node (ref "5V") (pin "1") (pinfunction "1_1") (pintype "passive"))
      (node (ref "5V") (pin "2") (pinfunction "2_2") (pintype "passive"))
      (node (ref "5VTERM") (pin "1") (pinfunction "1_1") (pintype "passive"))
      (node (ref "5VTERM") (pin "2") (pinfunction "2_2") (pintype "passive"))
      (node (ref "5VTERM") (pin "3") (pinfunction "3_3") (pintype "passive"))
      (node (ref "5V_JUMP") (pin "2") (pinfunction "2_2") (pintype "passive"))
      (node (ref "6.8UF") (pin "+") (pinfunction "1_+") (pintype "passive"))
      (node (ref "DALLASTERM") (pin "3") (pinfunction "3_3") (pintype "passive"))
      (node (ref "DS1307") (pin "8") (pinfunction "VCC_8") (pintype "power_in"))
      (node (ref "POWER") (pin "5") (pinfunction "5_5") (pintype "passive"))
      (node (ref "TN9POWTERM") (pin "1") (pinfunction "1_1") (pintype "passive"))
      (node (ref "U$11") (pin "2") (pinfunction "VCC_2") (pintype "power_in"))
      (node (ref "U$12") (pin "1") (pinfunction "VCC_1") (pintype "power_in"))
      (node (ref "U$12") (pin "7") (pinfunction "/SHDN_7") (pintype "input"))
      (node (ref "U$12") (pin "9") (pinfunction "VCC_9") (pintype "power_in"))
      (node (ref "U$14") (pin "8") (pinfunction "VCC_8") (pintype "power_in"))
      (node (ref "U$9") (pin "2") (pinfunction "VCC_2") (pintype "power_in"))
    )
    (net (code "104") (name "GND") (class "Default")
      (node (ref "0.1UF") (pin "2") (pinfunction "2_2") (pintype "passive"))
      (node (ref "0.1UF-2") (pin "2") (pinfunction "2_2") (pintype "passive"))
      (node (ref "0.1UF-3") (pin "1") (pinfunction "1_1") (pintype "passive"))
      (node (ref "0.1UF-4") (pin "2") (pinfunction "2_2") (pintype "passive"))
      (node (ref "0.1UF-5") (pin "2") (pinfunction "2_2") (pintype "passive"))
      (node (ref "0.5") (pin "1") (pinfunction "1_1") (pintype "passive"))
      (node (ref "100UF") (pin "-") (pinfunction "2_-") (pintype "passive"))
      (node (ref "100UF-2") (pin "-") (pinfunction "2_-") (pintype "passive"))
      (node (ref "10UF") (pin "-") (pinfunction "2_-") (pintype "passive"))
      (node (ref "10UF-2") (pin "-") (pinfunction "2_-") (pintype "passive"))
      (node (ref "10UF-LOWESR") (pin "-") (pinfunction "2_-") (pintype "passive"))
      (node (ref "1UF") (pin "1") (pinfunction "1_1") (pintype "passive"))
      (node (ref "6.8UF") (pin "-") (pinfunction "2_-") (pintype "passive"))
      (node (ref "8-13") (pin "4") (pinfunction "4_4") (pintype "passive"))
      (node (ref "BATT") (pin "-") (pinfunction "-_-") (pintype "passive"))
      (node (ref "BMP085TERM") (pin "5") (pinfunction "5_5") (pintype "passive"))
      (node (ref "DALLASTERM") (pin "1") (pinfunction "1_1") (pintype "passive"))
      (node (ref "DS1307") (pin "4") (pinfunction "GND_4") (pintype "power_in"))
      (node (ref "GNDTERM") (pin "1") (pinfunction "1_1") (pintype "passive"))
      (node (ref "GNDTERM") (pin "2") (pinfunction "2_2") (pintype "passive"))
      (node (ref "GNDTERM") (pin "3") (pinfunction "3_3") (pintype "passive"))
      (node (ref "LED1") (pin "K") (pinfunction "C_K") (pintype "passive"))
      (node (ref "LED2") (pin "K") (pinfunction "C_K") (pintype "passive"))
      (node (ref "OPA1TERM") (pin "2") (pinfunction "2_2") (pintype "passive"))
      (node (ref "POWER") (pin "6") (pinfunction "6_6") (pintype "passive"))
      (node (ref "POWER") (pin "7") (pinfunction "7_7") (pintype "passive"))
      (node (ref "PWRTERM") (pin "1") (pinfunction "1_1") (pintype "passive"))
      (node (ref "SDLVLS") (pin "1") (pinfunction "OE_1") (pintype "input"))
      (node (ref "SDLVLS") (pin "10") (pinfunction "OE_10") (pintype "input"))
      (node (ref "SDLVLS") (pin "4") (pinfunction "OE_4") (pintype "input"))
      (node (ref "SDLVLS") (pin "7") (pinfunction "GND_7") (pintype "power_in"))
      (node (ref "TN9POWTERM") (pin "2") (pinfunction "2_2") (pintype "passive"))
      (node (ref "U$1") (pin "3") (pinfunction "VSS1_3") (pintype "power_in"))
      (node (ref "U$1") (pin "6") (pinfunction "VSS2_6") (pintype "power_in"))
      (node (ref "U$1") (pin "GP") (pinfunction "GND_GP") (pintype "power_in"))
      (node (ref "U$1") (pin "GP3") (pinfunction "COMMON_SW_GP3") (pintype "passive"))
      (node (ref "U$11") (pin "4") (pinfunction "GND_4") (pintype "power_in"))
      (node (ref "U$12") (pin "10") (pinfunction "GND_10") (pintype "power_in"))
      (node (ref "U$12") (pin "11") (pinfunction "MODE_11") (pintype "input"))
      (node (ref "U$12") (pin "6") (pinfunction "COM_6") (pintype "input"))
      (node (ref "U$14") (pin "3") (pinfunction "+IN_3") (pintype "input"))
      (node (ref "U$14") (pin "4") (pinfunction "GND_4") (pintype "power_in"))
      (node (ref "U$16") (pin "1") (pinfunction "1_1") (pintype "passive"))
      (node (ref "U$16") (pin "2") (pinfunction "2_2") (pintype "passive"))
      (node (ref "U$18") (pin "3") (pinfunction "GND_3") (pintype "power_in"))
      (node (ref "U$18") (pin "4") (pinfunction "EN_4") (pintype "input"))
      (node (ref "U$4") (pin "1") (pinfunction "1_1") (pintype "passive"))
      (node (ref "U$9") (pin "1") (pinfunction "GND_1") (pintype "power_in"))
      (node (ref "ZENER") (pin "A") (pinfunction "A_A") (pintype "passive"))
    )
    (net (code "105") (name "Net-(1K-Pad1)") (class "Default")
      (node (ref "1K") (pin "1") (pinfunction "1_1") (pintype "passive"))
      (node (ref "LED1") (pin "A") (pinfunction "A_A") (pintype "passive"))
    )
    (net (code "106") (name "Net-(1K_2-Pad1)") (class "Default")
      (node (ref "1K_2") (pin "1") (pinfunction "1_1") (pintype "passive"))
      (node (ref "LED2") (pin "A") (pinfunction "A_A") (pintype "passive"))
    )
    (net (code "107") (name "Net-(10UF-T-2)") (class "Default")
      (node (ref "0.5") (pin "2") (pinfunction "2_2") (pintype "passive"))
      (node (ref "10UF-T") (pin "-") (pinfunction "2_-") (pintype "passive"))
    )
    (net (code "108") (name "Net-(GND-Pad1)") (class "Default")
      (node (ref "GND") (pin "1") (pinfunction "1_1") (pintype "passive"))
      (node (ref "GND") (pin "2") (pinfunction "2_2") (pintype "passive"))
    )
    (net (code "109") (name "Net-(U$11-TRIM)") (class "Default")
      (node (ref "1UF") (pin "2") (pinfunction "2_2") (pintype "passive"))
      (node (ref "U$11") (pin "5") (pinfunction "TRIM_5") (pintype "bidirectional"))
    )
    (net (code "110") (name "Net-(U$12-CH1)") (class "Default")
      (node (ref "ADCTERM") (pin "1") (pinfunction "1_1") (pintype "passive"))
      (node (ref "U$12") (pin "3") (pinfunction "CH1_3") (pintype "input"))
    )
    (net (code "111") (name "Net-(U$12-CH2)") (class "Default")
      (node (ref "ADCTERM") (pin "2") (pinfunction "2_2") (pintype "passive"))
      (node (ref "U$12") (pin "4") (pinfunction "CH2_4") (pintype "input"))
    )
    (net (code "112") (name "Net-(U$12-CH3)") (class "Default")
      (node (ref "ADCTERM") (pin "3") (pinfunction "3_3") (pintype "passive"))
      (node (ref "U$12") (pin "5") (pinfunction "CH3_5") (pintype "input"))
    )
    (net (code "113") (name "Net-(U$14B-+IN)") (class "Default")
      (node (ref "OPA2TERM") (pin "1") (pinfunction "1_1") (pintype "passive"))
      (node (ref "U$14") (pin "5") (pinfunction "+IN_5") (pintype "input"))
    )
    (net (code "114") (name "Net-(U$14B--IN)") (class "Default")
      (node (ref "OPA2TERM") (pin "2") (pinfunction "2_2") (pintype "passive"))
      (node (ref "U$14") (pin "6") (pinfunction "-IN_6") (pintype "input"))
    )
    (net (code "115") (name "Net-(U$14B-OUT)") (class "Default")
      (node (ref "OPA2TERM") (pin "3") (pinfunction "3_3") (pintype "passive"))
      (node (ref "U$14") (pin "7") (pinfunction "OUT_7") (pintype "output"))
    )
    (net (code "116") (name "Net-(U$18-RESET)") (class "Default")
      (node (ref "250K") (pin "1") (pinfunction "1_1") (pintype "passive"))
      (node (ref "U$18") (pin "2") (pinfunction "RESET_2") (pintype "bidirectional"))
    )
    (net (code "117") (name "unconnected-(BATT-+-Pad+1)") (class "Default")
      (node (ref "BATT") (pin "+1") (pinfunction "+_+1") (pintype "passive"))
    )
    (net (code "118") (name "unconnected-(OPAMPEXTRA1-Pad1)") (class "Default")
      (node (ref "OPAMPEXTRA1") (pin "1") (pinfunction "1_1") (pintype "passive"))
    )
    (net (code "119") (name "unconnected-(OPAMPEXTRA1-Pad2)") (class "Default")
      (node (ref "OPAMPEXTRA1") (pin "2") (pinfunction "2_2") (pintype "passive"))
    )
    (net (code "120") (name "unconnected-(OPAMPEXTRA1-Pad3)") (class "Default")
      (node (ref "OPAMPEXTRA1") (pin "3") (pinfunction "3_3") (pintype "passive"))
    )
    (net (code "121") (name "unconnected-(OPAMPEXTRA2-Pad1)") (class "Default")
      (node (ref "OPAMPEXTRA2") (pin "1") (pinfunction "1_1") (pintype "passive"))
    )
    (net (code "122") (name "unconnected-(OPAMPEXTRA2-Pad2)") (class "Default")
      (node (ref "OPAMPEXTRA2") (pin "2") (pinfunction "2_2") (pintype "passive"))
    )
    (net (code "123") (name "unconnected-(OPAMPEXTRA2-Pad3)") (class "Default")
      (node (ref "OPAMPEXTRA2") (pin "3") (pinfunction "3_3") (pintype "passive"))
    )
    (net (code "124") (name "unconnected-(PWRSWTCH-S-Pad3)") (class "Default")
      (node (ref "PWRSWTCH") (pin "3") (pinfunction "S_3") (pintype "passive"))
    )
    (net (code "125") (name "unconnected-(SDLVLSD-A-Pad12)") (class "Default")
      (node (ref "SDLVLS") (pin "12") (pinfunction "A_12") (pintype "input"))
    )
    (net (code "126") (name "unconnected-(SDLVLSD-Y-Pad11)") (class "Default")
      (node (ref "SDLVLS") (pin "11") (pinfunction "Y_11") (pintype "tri_state"))
    )
    (net (code "127") (name "unconnected-(U$1-DAT1-Pad8)") (class "Default")
      (node (ref "U$1") (pin "8") (pinfunction "DAT1_8") (pintype "bidirectional"))
    )
    (net (code "128") (name "unconnected-(U$1-DAT2-Pad9)") (class "Default")
      (node (ref "U$1") (pin "9") (pinfunction "DAT2_9") (pintype "bidirectional"))
    )
    (net (code "129") (name "unconnected-(U$11-DNC-Pad1)") (class "Default")
      (node (ref "U$11") (pin "1") (pinfunction "DNC_1") (pintype "no_connect"))
    )
    (net (code "130") (name "unconnected-(U$11-DNC2-Pad8)") (class "Default")
      (node (ref "U$11") (pin "8") (pinfunction "DNC2_8") (pintype "no_connect"))
    )
    (net (code "131") (name "unconnected-(U$11-NC-Pad7)") (class "Default")
      (node (ref "U$11") (pin "7") (pinfunction "NC_7") (pintype "no_connect"))
    )
    (net (code "132") (name "unconnected-(U$11-TEMP-Pad3)") (class "Default")
      (node (ref "U$11") (pin "3") (pinfunction "TEMP_3") (pintype "bidirectional"))
    )
  )
)
